# Leptons.net
KiCad netlist of a schematic drawn in Altium Designer
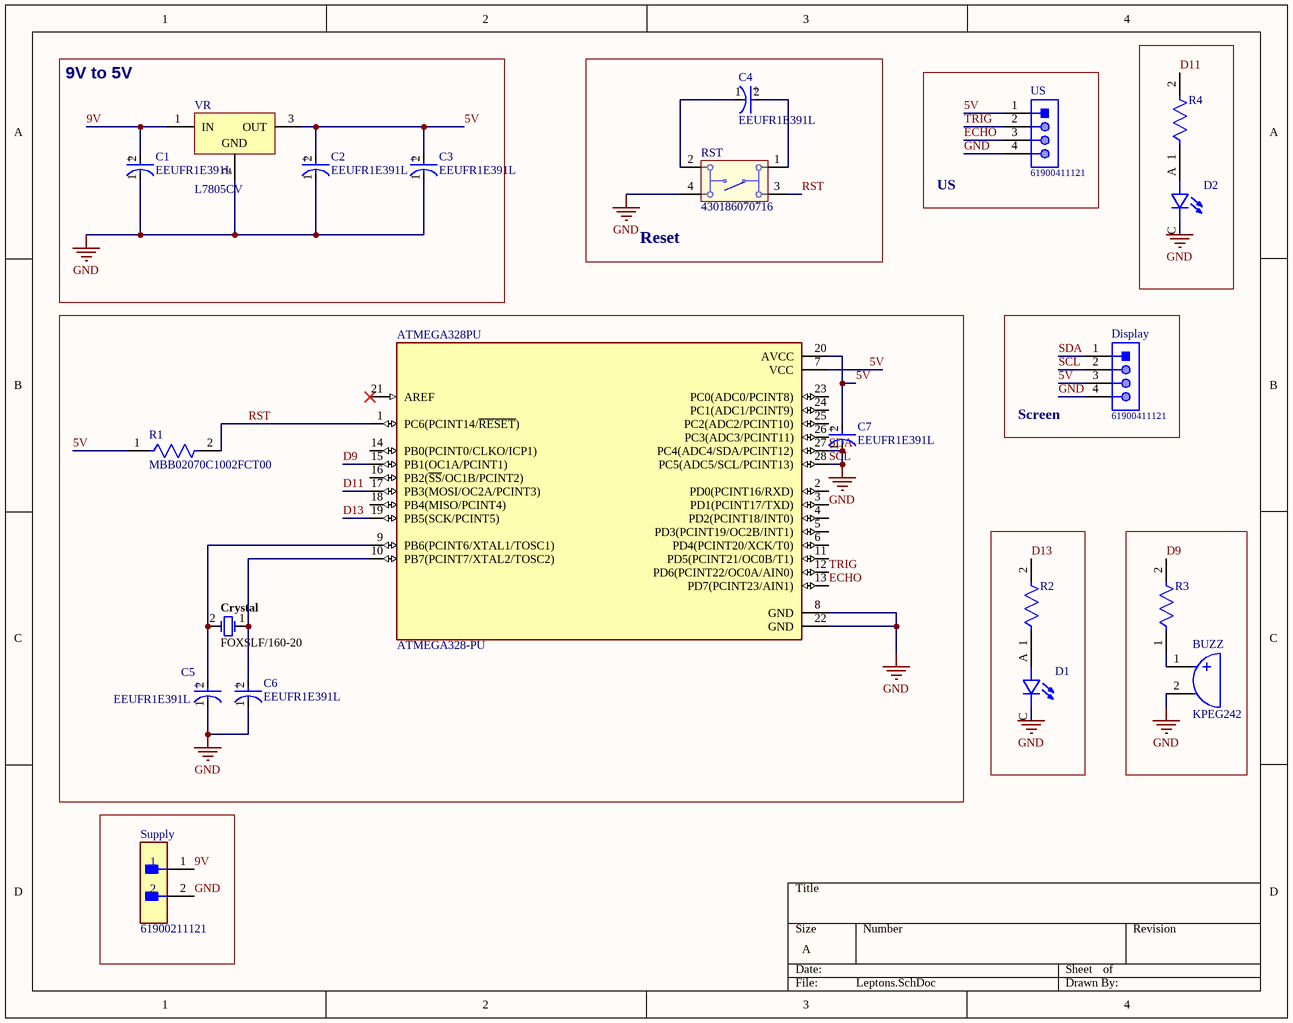
[diagram p0: Leptons.SchDoc]

(export (version "E")
  (design (tool "Eeschema 10.0.6"))
  (components
    (comp (ref "ATMEGA328PU")
      (value "ATMEGA328-PU")
      (footprint "DIP787W46P254L3467H508Q28")
      (description "AVR AVRÂ® ATmega Microcontroller IC 8-Bit 20MHz 32KB (16K x 16) FLASH 28-PDIP")
      (fields (field (name "MF") "Microchip"))
      (libsource (lib "ATMEGA328-PU") (part "ATMEGA328-PU"))
    )
    (comp (ref "BUZZ")
      (value "KPEG242")
      (footprint "KINGS-KPEG242-2")
      (description "Piezo Indicator, 4100 Hz, 3 to 16 V, -20 to 70 degC, 2-Pin THD, RoHS")
      (fields (field (name "PARTNUMBER") "KPE-242") (field (name "MANUFACTURER") "KingstateElectronicsCorp."))
      (libsource (lib "Altium Content Vault") (part "KINGS-KPEG242-2"))
    )
    (comp (ref "C1")
      (value "EEUFR1E391L")
      (footprint "FP-RAD-TH-D_8_0_5-L_15_1-MFG")
      (description "Aluminum Electrolytic Capacitors (Radial Lead Type) 390uF ±20% 25V")
      (fields (field (name "TOLERANCE") "20%") (field (name "VOLTAGE") "25V"))
      (libsource (lib "Altium Content Vault") (part "a00bbbee19879c290e62620ae7e47b1"))
    )
    (comp (ref "C2")
      (value "EEUFR1E391L")
      (footprint "FP-RAD-TH-D_8_0_5-L_15_1-MFG")
      (description "Aluminum Electrolytic Capacitors (Radial Lead Type) 390uF ±20% 25V")
      (fields (field (name "TOLERANCE") "20%") (field (name "VOLTAGE") "25V"))
      (libsource (lib "Altium Content Vault") (part "a00bbbee19879c290e62620ae7e47b1"))
    )
    (comp (ref "C3")
      (value "EEUFR1E391L")
      (footprint "FP-RAD-TH-D_8_0_5-L_15_1-MFG")
      (description "Aluminum Electrolytic Capacitors (Radial Lead Type) 390uF ±20% 25V")
      (fields (field (name "TOLERANCE") "20%") (field (name "VOLTAGE") "25V"))
      (libsource (lib "Altium Content Vault") (part "a00bbbee19879c290e62620ae7e47b1"))
    )
    (comp (ref "C4")
      (value "EEUFR1E391L")
      (footprint "FP-RAD-TH-D_8_0_5-L_15_1-MFG")
      (description "Aluminum Electrolytic Capacitors (Radial Lead Type) 390uF ±20% 25V")
      (fields (field (name "TOLERANCE") "20%") (field (name "VOLTAGE") "25V"))
      (libsource (lib "Altium Content Vault") (part "a00bbbee19879c290e62620ae7e47b1"))
    )
    (comp (ref "C5")
      (value "EEUFR1E391L")
      (footprint "FP-RAD-TH-D_8_0_5-L_15_1-MFG")
      (description "Aluminum Electrolytic Capacitors (Radial Lead Type) 390uF ±20% 25V")
      (fields (field (name "TOLERANCE") "20%") (field (name "VOLTAGE") "25V"))
      (libsource (lib "Altium Content Vault") (part "a00bbbee19879c290e62620ae7e47b1"))
    )
    (comp (ref "C6")
      (value "EEUFR1E391L")
      (footprint "FP-RAD-TH-D_8_0_5-L_15_1-MFG")
      (description "Aluminum Electrolytic Capacitors (Radial Lead Type) 390uF ±20% 25V")
      (fields (field (name "TOLERANCE") "20%") (field (name "VOLTAGE") "25V"))
      (libsource (lib "Altium Content Vault") (part "a00bbbee19879c290e62620ae7e47b1"))
    )
    (comp (ref "C7")
      (value "EEUFR1E391L")
      (footprint "FP-RAD-TH-D_8_0_5-L_15_1-MFG")
      (description "Aluminum Electrolytic Capacitors (Radial Lead Type) 390uF ±20% 25V")
      (fields (field (name "TOLERANCE") "20%") (field (name "VOLTAGE") "25V"))
      (libsource (lib "Altium Content Vault") (part "a00bbbee19879c290e62620ae7e47b1"))
    )
    (comp (ref "Crystal")
      (value "FOXSLF/160-20")
      (footprint "FOX-FOXSLF160-20")
      (description "Resistance Weld Thru-Hole Crystal, 16 MHz, -20 to 70 degC, 2-Pin THD, RoHS, Bulk")
      (fields (field (name "TOLERANCE") "1%"))
      (libsource (lib "Altium Content Vault") (part "XTAL-1-2-2"))
    )
    (comp (ref "D1")
      (value "L08R5000Q1")
      (footprint "LEDRD254W57D500H1070")
      (fields (field (name "MF") "LED Technology"))
      (libsource (lib "L08R5000Q1") (part "L08R5000Q1"))
    )
    (comp (ref "D2")
      (value "L08R5000Q1")
      (footprint "LEDRD254W57D500H1070")
      (fields (field (name "MF") "LED Technology"))
      (libsource (lib "L08R5000Q1") (part "L08R5000Q1"))
    )
    (comp (ref "Display")
      (value "61900411121")
      (footprint "61900411121")
      (description "Male Locking Header WR-WTB, THT, Vertical, pitch 2.54 mm, 1 x 4 position")
      (fields (field (name "MANUFACTURER") "Wurth Elektronik") (field (name "PUBLISHER") "WurthElektronik"))
      (libsource (lib "Altium Content Vault") (part "WE-CN-1P-M-R4"))
    )
    (comp (ref "R1")
      (value "MBB02070C1002FCT00")
      (footprint "FP-MBB0207-MFG")
      (description "RES 10K OHM 0.6W 1% AXIAL")
      (fields (field (name "TOLERANCE") "1%"))
      (libsource (lib "Altium Content Vault") (part "1029c3af85768c4190bb7ad29bc67b5"))
    )
    (comp (ref "R2")
      (value "MBB02070C1002FCT00")
      (footprint "FP-MBB0207-MFG")
      (description "RES 10K OHM 0.6W 1% AXIAL")
      (fields (field (name "TOLERANCE") "1%"))
      (libsource (lib "Altium Content Vault") (part "1029c3af85768c4190bb7ad29bc67b5"))
    )
    (comp (ref "R3")
      (value "MBB02070C1002FCT00")
      (footprint "FP-MBB0207-MFG")
      (description "RES 10K OHM 0.6W 1% AXIAL")
      (fields (field (name "TOLERANCE") "1%"))
      (libsource (lib "Altium Content Vault") (part "1029c3af85768c4190bb7ad29bc67b5"))
    )
    (comp (ref "R4")
      (value "MBB02070C1002FCT00")
      (footprint "FP-MBB0207-MFG")
      (description "RES 10K OHM 0.6W 1% AXIAL")
      (fields (field (name "TOLERANCE") "1%"))
      (libsource (lib "Altium Content Vault") (part "1029c3af85768c4190bb7ad29bc67b5"))
    )
    (comp (ref "RST")
      (value "430186070716")
      (footprint "430186070716")
      (description "WS-TATV THT Tact Switch 6X6 mm")
      (fields (field (name "MANUFACTURER") "Wuerth Elektronik"))
      (libsource (lib "Altium Content Vault") (part "WE-TACT-SW-4"))
    )
    (comp (ref "Supply")
      (value "61900211121")
      (footprint "FP-61900211121-MFG")
      (description "CONN HEADER VERT 2POS 2.54MM")
      (libsource (lib "Altium Content Vault") (part "3bc925449376181038e59eaffc5286c"))
    )
    (comp (ref "US")
      (value "61900411121")
      (footprint "61900411121")
      (description "Male Locking Header WR-WTB, THT, Vertical, pitch 2.54 mm, 1 x 4 position")
      (fields (field (name "MANUFACTURER") "Wurth Elektronik") (field (name "PUBLISHER") "WurthElektronik"))
      (libsource (lib "Altium Content Vault") (part "WE-CN-1P-M-R4"))
    )
    (comp (ref "VR")
      (value "L7805CV")
      (footprint "TO220")
      (description "Positive Voltage Regulator, 5V, 3-Pin TO-220")
      (libsource (lib "Altium Content Vault") (part "PM-REG-L4940-SIL3"))
    )
  )
  (nets
    (net (code "1") (name "/5V") (class "Default")
      (node (ref "ATMEGA328PU") (pin "20") (pinfunction "AVCC_20") (pintype "power_in"))
      (node (ref "ATMEGA328PU") (pin "7") (pinfunction "VCC_7") (pintype "power_in"))
      (node (ref "C2") (pin "2") (pinfunction "A_2") (pintype "passive"))
      (node (ref "C3") (pin "2") (pinfunction "A_2") (pintype "passive"))
      (node (ref "C7") (pin "2") (pinfunction "A_2") (pintype "passive"))
      (node (ref "Display") (pin "3") (pinfunction "3_3") (pintype "passive"))
      (node (ref "R1") (pin "1") (pinfunction "1_1") (pintype "passive"))
      (node (ref "US") (pin "1") (pinfunction "1_1") (pintype "passive"))
      (node (ref "VR") (pin "3") (pinfunction "OUT_3") (pintype "power_in"))
    )
    (net (code "2") (name "/9V") (class "Default")
      (node (ref "C1") (pin "2") (pinfunction "A_2") (pintype "passive"))
      (node (ref "Supply") (pin "1") (pinfunction "1_1") (pintype "passive"))
      (node (ref "VR") (pin "1") (pinfunction "IN_1") (pintype "power_in"))
    )
    (net (code "3") (name "/D9") (class "Default")
      (node (ref "ATMEGA328PU") (pin "15") (pinfunction "PB1(OC1A/PCINT1)_15") (pintype "bidirectional"))
      (node (ref "R3") (pin "2") (pinfunction "2_2") (pintype "passive"))
    )
    (net (code "4") (name "/D11") (class "Default")
      (node (ref "ATMEGA328PU") (pin "17") (pinfunction "PB3(MOSI/OC2A/PCINT3)_17") (pintype "bidirectional"))
      (node (ref "R4") (pin "2") (pinfunction "2_2") (pintype "passive"))
    )
    (net (code "5") (name "/D13") (class "Default")
      (node (ref "ATMEGA328PU") (pin "19") (pinfunction "PB5(SCK/PCINT5)_19") (pintype "bidirectional"))
      (node (ref "R2") (pin "2") (pinfunction "2_2") (pintype "passive"))
    )
    (net (code "6") (name "/ECHO") (class "Default")
      (node (ref "ATMEGA328PU") (pin "13") (pinfunction "PD7(PCINT23/AIN1)_13") (pintype "bidirectional"))
      (node (ref "US") (pin "3") (pinfunction "3_3") (pintype "passive"))
    )
    (net (code "7") (name "/RST") (class "Default")
      (node (ref "ATMEGA328PU") (pin "1") (pinfunction "PC6(PCINT14/~{RESET})_1") (pintype "bidirectional"))
      (node (ref "R1") (pin "2") (pinfunction "2_2") (pintype "passive"))
      (node (ref "RST") (pin "3") (pinfunction "3_3") (pintype "passive"))
    )
    (net (code "8") (name "/TRIG") (class "Default")
      (node (ref "ATMEGA328PU") (pin "12") (pinfunction "PD6(PCINT22/OC0A/AIN0)_12") (pintype "bidirectional"))
      (node (ref "US") (pin "2") (pinfunction "2_2") (pintype "passive"))
    )
    (net (code "9") (name "GND") (class "Default")
      (node (ref "ATMEGA328PU") (pin "22") (pinfunction "GND_22") (pintype "power_in"))
      (node (ref "ATMEGA328PU") (pin "27") (pinfunction "PC4(ADC4/SDA/PCINT12)_27") (pintype "bidirectional"))
      (node (ref "ATMEGA328PU") (pin "28") (pinfunction "PC5(ADC5/SCL/PCINT13)_28") (pintype "bidirectional"))
      (node (ref "ATMEGA328PU") (pin "8") (pinfunction "GND_8") (pintype "power_in"))
      (node (ref "BUZZ") (pin "2") (pinfunction "2_2") (pintype "passive"))
      (node (ref "C1") (pin "1") (pinfunction "C_1") (pintype "passive"))
      (node (ref "C2") (pin "1") (pinfunction "C_1") (pintype "passive"))
      (node (ref "C3") (pin "1") (pinfunction "C_1") (pintype "passive"))
      (node (ref "C5") (pin "1") (pinfunction "C_1") (pintype "passive"))
      (node (ref "C6") (pin "1") (pinfunction "C_1") (pintype "passive"))
      (node (ref "C7") (pin "1") (pinfunction "C_1") (pintype "passive"))
      (node (ref "D1") (pin "C") (pinfunction "C_C") (pintype "passive"))
      (node (ref "D2") (pin "C") (pinfunction "C_C") (pintype "passive"))
      (node (ref "Display") (pin "1") (pinfunction "1_1") (pintype "passive"))
      (node (ref "Display") (pin "2") (pinfunction "2_2") (pintype "passive"))
      (node (ref "Display") (pin "4") (pinfunction "4_4") (pintype "passive"))
      (node (ref "RST") (pin "4") (pinfunction "4_4") (pintype "passive"))
      (node (ref "Supply") (pin "2") (pinfunction "2_2") (pintype "passive"))
      (node (ref "US") (pin "4") (pinfunction "4_4") (pintype "passive"))
      (node (ref "VR") (pin "2") (pinfunction "GND_2") (pintype "power_in"))
    )
    (net (code "10") (name "Net-(ATMEGA328PU-PB6(PCINT6{slash}XTAL1{slash}TOSC1))") (class "Default")
      (node (ref "ATMEGA328PU") (pin "9") (pinfunction "PB6(PCINT6/XTAL1/TOSC1)_9") (pintype "bidirectional"))
      (node (ref "C5") (pin "2") (pinfunction "A_2") (pintype "passive"))
      (node (ref "Crystal") (pin "2") (pinfunction "2_2") (pintype "passive"))
    )
    (net (code "11") (name "Net-(ATMEGA328PU-PB7(PCINT7{slash}XTAL2{slash}TOSC2))") (class "Default")
      (node (ref "ATMEGA328PU") (pin "10") (pinfunction "PB7(PCINT7/XTAL2/TOSC2)_10") (pintype "bidirectional"))
      (node (ref "C6") (pin "2") (pinfunction "A_2") (pintype "passive"))
      (node (ref "Crystal") (pin "1") (pinfunction "1_1") (pintype "passive"))
    )
    (net (code "12") (name "Net-(BUZZ-Pad1)") (class "Default")
      (node (ref "BUZZ") (pin "1") (pinfunction "1_1") (pintype "passive"))
      (node (ref "R3") (pin "1") (pinfunction "1_1") (pintype "passive"))
    )
    (net (code "13") (name "Net-(C4-A)") (class "Default")
      (node (ref "C4") (pin "2") (pinfunction "A_2") (pintype "passive"))
      (node (ref "RST") (pin "1") (pinfunction "1_1") (pintype "passive"))
    )
    (net (code "14") (name "Net-(C4-C)") (class "Default")
      (node (ref "C4") (pin "1") (pinfunction "C_1") (pintype "passive"))
      (node (ref "RST") (pin "2") (pinfunction "2_2") (pintype "passive"))
    )
    (net (code "15") (name "Net-(D1-PadA)") (class "Default")
      (node (ref "D1") (pin "A") (pinfunction "A_A") (pintype "passive"))
      (node (ref "R2") (pin "1") (pinfunction "1_1") (pintype "passive"))
    )
    (net (code "16") (name "Net-(D2-PadA)") (class "Default")
      (node (ref "D2") (pin "A") (pinfunction "A_A") (pintype "passive"))
      (node (ref "R4") (pin "1") (pinfunction "1_1") (pintype "passive"))
    )
    (net (code "17") (name "unconnected-(ATMEGA328PU-AREF-Pad21)") (class "Default")
      (node (ref "ATMEGA328PU") (pin "21") (pinfunction "AREF_21") (pintype "input+no_connect"))
    )
    (net (code "18") (name "unconnected-(ATMEGA328PU-PB0(PCINT0{slash}CLKO{slash}ICP1)-Pad14)") (class "Default")
      (node (ref "ATMEGA328PU") (pin "14") (pinfunction "PB0(PCINT0/CLKO/ICP1)_14") (pintype "bidirectional"))
    )
    (net (code "19") (name "unconnected-(ATMEGA328PU-PB2(~{SS}{slash}OC1B{slash}PCINT2)-Pad16)") (class "Default")
      (node (ref "ATMEGA328PU") (pin "16") (pinfunction "PB2(~{SS}/OC1B/PCINT2)_16") (pintype "bidirectional"))
    )
    (net (code "20") (name "unconnected-(ATMEGA328PU-PB4(MISO{slash}PCINT4)-Pad18)") (class "Default")
      (node (ref "ATMEGA328PU") (pin "18") (pinfunction "PB4(MISO/PCINT4)_18") (pintype "bidirectional"))
    )
    (net (code "21") (name "unconnected-(ATMEGA328PU-PC0(ADC0{slash}PCINT8)-Pad23)") (class "Default")
      (node (ref "ATMEGA328PU") (pin "23") (pinfunction "PC0(ADC0/PCINT8)_23") (pintype "bidirectional"))
    )
    (net (code "22") (name "unconnected-(ATMEGA328PU-PC1(ADC1{slash}PCINT9)-Pad24)") (class "Default")
      (node (ref "ATMEGA328PU") (pin "24") (pinfunction "PC1(ADC1/PCINT9)_24") (pintype "bidirectional"))
    )
    (net (code "23") (name "unconnected-(ATMEGA328PU-PC2(ADC2{slash}PCINT10)-Pad25)") (class "Default")
      (node (ref "ATMEGA328PU") (pin "25") (pinfunction "PC2(ADC2/PCINT10)_25") (pintype "bidirectional"))
    )
    (net (code "24") (name "unconnected-(ATMEGA328PU-PC3(ADC3{slash}PCINT11)-Pad26)") (class "Default")
      (node (ref "ATMEGA328PU") (pin "26") (pinfunction "PC3(ADC3/PCINT11)_26") (pintype "bidirectional"))
    )
    (net (code "25") (name "unconnected-(ATMEGA328PU-PD0(PCINT16{slash}RXD)-Pad2)") (class "Default")
      (node (ref "ATMEGA328PU") (pin "2") (pinfunction "PD0(PCINT16/RXD)_2") (pintype "bidirectional"))
    )
    (net (code "26") (name "unconnected-(ATMEGA328PU-PD1(PCINT17{slash}TXD)-Pad3)") (class "Default")
      (node (ref "ATMEGA328PU") (pin "3") (pinfunction "PD1(PCINT17/TXD)_3") (pintype "bidirectional"))
    )
    (net (code "27") (name "unconnected-(ATMEGA328PU-PD2(PCINT18{slash}INT0)-Pad4)") (class "Default")
      (node (ref "ATMEGA328PU") (pin "4") (pinfunction "PD2(PCINT18/INT0)_4") (pintype "bidirectional"))
    )
    (net (code "28") (name "unconnected-(ATMEGA328PU-PD3(PCINT19{slash}OC2B{slash}INT1)-Pad5)") (class "Default")
      (node (ref "ATMEGA328PU") (pin "5") (pinfunction "PD3(PCINT19/OC2B/INT1)_5") (pintype "bidirectional"))
    )
    (net (code "29") (name "unconnected-(ATMEGA328PU-PD4(PCINT20{slash}XCK{slash}T0)-Pad6)") (class "Default")
      (node (ref "ATMEGA328PU") (pin "6") (pinfunction "PD4(PCINT20/XCK/T0)_6") (pintype "bidirectional"))
    )
    (net (code "30") (name "unconnected-(ATMEGA328PU-PD5(PCINT21{slash}OC0B{slash}T1)-Pad11)") (class "Default")
      (node (ref "ATMEGA328PU") (pin "11") (pinfunction "PD5(PCINT21/OC0B/T1)_11") (pintype "bidirectional"))
    )
  )
)
